# USB_Charger.net
KiCad netlist of a schematic drawn in EAGLE
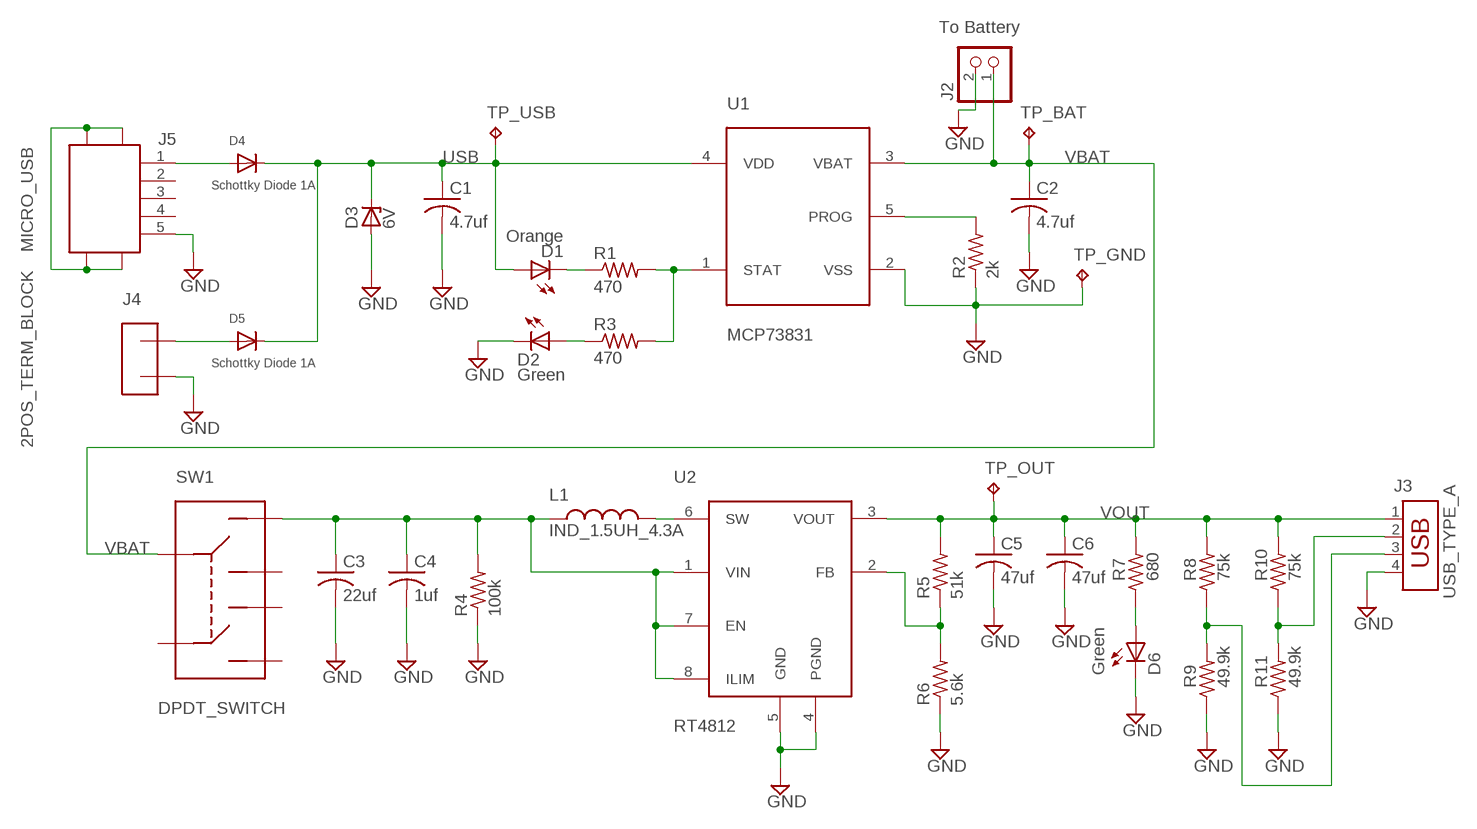
[diagram p0: schematic, sheet 1]

(export (version "E")
  (design (tool "Eeschema 10.0.6"))
  (components
    (comp (ref "C1")
      (value "4.7uf")
      (footprint "eagle-import:C0805")
      (libsource (lib "eagle-import") (part "C-USC0805"))
    )
    (comp (ref "C2")
      (value "4.7uf")
      (footprint "eagle-import:C0805")
      (libsource (lib "eagle-import") (part "C-USC0805"))
    )
    (comp (ref "C3")
      (value "22uf")
      (footprint "eagle-import:C0805")
      (libsource (lib "eagle-import") (part "C-USC0805"))
    )
    (comp (ref "C4")
      (value "1uf")
      (footprint "eagle-import:C0805")
      (libsource (lib "eagle-import") (part "C-USC0805"))
    )
    (comp (ref "C5")
      (value "47uf")
      (footprint "eagle-import:C1210")
      (libsource (lib "eagle-import") (part "C-USC1210"))
    )
    (comp (ref "C6")
      (value "47uf")
      (footprint "eagle-import:C1210")
      (libsource (lib "eagle-import") (part "C-USC1210"))
    )
    (comp (ref "D1")
      (value "Orange")
      (footprint "eagle-import:CHIP-LED0805")
      (libsource (lib "eagle-import") (part "LEDCHIP-LED0805"))
    )
    (comp (ref "D2")
      (value "Green")
      (footprint "eagle-import:CHIP-LED0805")
      (libsource (lib "eagle-import") (part "LEDCHIP-LED0805"))
    )
    (comp (ref "D3")
      (value "6V")
      (footprint "eagle-import:SMB")
      (libsource (lib "eagle-import") (part "ZENER-DIODESMB"))
    )
    (comp (ref "D4")
      (value "Schottky Diode 1A")
      (footprint "eagle-import:SMADIODE")
      (libsource (lib "eagle-import") (part "DIODESMA"))
    )
    (comp (ref "D5")
      (value "Schottky Diode 1A")
      (footprint "eagle-import:SMADIODE")
      (libsource (lib "eagle-import") (part "DIODESMA"))
    )
    (comp (ref "D6")
      (value "Green")
      (footprint "eagle-import:CHIP-LED0805")
      (libsource (lib "eagle-import") (part "LEDCHIP-LED0805"))
    )
    (comp (ref "J2")
      (value "To Battery")
      (footprint "eagle-import:JST-PH-2-THM-RA")
      (libsource (lib "eagle-import") (part "JST_2PIN-THM-RA"))
    )
    (comp (ref "J3")
      (value "USB_TYPE_A")
      (footprint "eagle-import:USB")
      (libsource (lib "eagle-import") (part "USB-787616"))
    )
    (comp (ref "J4")
      (value "2POS_TERM_BLOCK")
      (footprint "eagle-import:2POS_5.08MM")
      (libsource (lib "eagle-import") (part "2POS_TERM_BLOCK"))
    )
    (comp (ref "J5")
      (value "MICRO_USB")
      (footprint "eagle-import:MICRO_USB")
      (libsource (lib "eagle-import") (part "MICRO_USB"))
    )
    (comp (ref "L1")
      (value "IND_1.5UH_4.3A")
      (footprint "eagle-import:IND_SMD")
      (libsource (lib "eagle-import") (part "IND_1.5UH_4.3A"))
    )
    (comp (ref "R1")
      (value "470")
      (footprint "eagle-import:R0805")
      (libsource (lib "eagle-import") (part "R-US_R0805"))
    )
    (comp (ref "R2")
      (value "2k")
      (footprint "eagle-import:R0805")
      (libsource (lib "eagle-import") (part "R-US_R0805"))
    )
    (comp (ref "R3")
      (value "470")
      (footprint "eagle-import:R0805")
      (libsource (lib "eagle-import") (part "R-US_R0805"))
    )
    (comp (ref "R4")
      (value "100k")
      (footprint "eagle-import:R0805")
      (libsource (lib "eagle-import") (part "R-US_R0805"))
    )
    (comp (ref "R5")
      (value "51k")
      (footprint "eagle-import:R0805")
      (libsource (lib "eagle-import") (part "R-US_R0805"))
    )
    (comp (ref "R6")
      (value "5.6k")
      (footprint "eagle-import:R0805")
      (libsource (lib "eagle-import") (part "R-US_R0805"))
    )
    (comp (ref "R7")
      (value "680")
      (footprint "eagle-import:R0805")
      (libsource (lib "eagle-import") (part "R-US_R0805"))
    )
    (comp (ref "R8")
      (value "75k")
      (footprint "eagle-import:R0805")
      (libsource (lib "eagle-import") (part "R-US_R0805"))
    )
    (comp (ref "R9")
      (value "49.9k")
      (footprint "eagle-import:R0805")
      (libsource (lib "eagle-import") (part "R-US_R0805"))
    )
    (comp (ref "R10")
      (value "75k")
      (footprint "eagle-import:R0805")
      (libsource (lib "eagle-import") (part "R-US_R0805"))
    )
    (comp (ref "R11")
      (value "49.9k")
      (footprint "eagle-import:R0805")
      (libsource (lib "eagle-import") (part "R-US_R0805"))
    )
    (comp (ref "SW1")
      (value "DPDT_SWITCH")
      (footprint "eagle-import:GF-126-0159")
      (libsource (lib "eagle-import") (part "DPDT_SWITCH"))
    )
    (comp (ref "TP_BAT")
      (value "TPB1,27")
      (footprint "eagle-import:B1,27")
      (libsource (lib "eagle-import") (part "TPB1,27"))
    )
    (comp (ref "TP_GND")
      (value "TPB1,27")
      (footprint "eagle-import:B1,27")
      (libsource (lib "eagle-import") (part "TPB1,27"))
    )
    (comp (ref "TP_OUT")
      (value "TPB1,27")
      (footprint "eagle-import:B1,27")
      (libsource (lib "eagle-import") (part "TPB1,27"))
    )
    (comp (ref "TP_USB")
      (value "TPB1,27")
      (footprint "eagle-import:B1,27")
      (libsource (lib "eagle-import") (part "TPB1,27"))
    )
    (comp (ref "U1")
      (value "MCP73831")
      (footprint "eagle-import:SOT-23-5")
      (libsource (lib "eagle-import") (part "MCP73831"))
    )
    (comp (ref "U2")
      (value "RT4812")
      (footprint "eagle-import:TSOT-23-8")
      (libsource (lib "eagle-import") (part "RT4812"))
    )
  )
  (nets
    (net (code "1") (name "/USB") (class "Default")
      (node (ref "C1") (pin "1") (pinfunction "1_1") (pintype "passive"))
      (node (ref "D1") (pin "A") (pinfunction "A_A") (pintype "passive"))
      (node (ref "D3") (pin "C") (pinfunction "C_C") (pintype "passive"))
      (node (ref "D4") (pin "C") (pinfunction "C_C") (pintype "passive"))
      (node (ref "D5") (pin "C") (pinfunction "C_C") (pintype "passive"))
      (node (ref "TP_USB") (pin "TP") (pinfunction "TP_TP") (pintype "input"))
      (node (ref "U1") (pin "4") (pinfunction "VDD_4") (pintype "bidirectional"))
    )
    (net (code "2") (name "/VBAT") (class "Default")
      (node (ref "C2") (pin "1") (pinfunction "1_1") (pintype "passive"))
      (node (ref "J2") (pin "1") (pinfunction "2_1") (pintype "passive"))
      (node (ref "SW1") (pin "2") (pinfunction "2_2") (pintype "bidirectional"))
      (node (ref "TP_BAT") (pin "TP") (pinfunction "TP_TP") (pintype "input"))
      (node (ref "U1") (pin "3") (pinfunction "VBAT_3") (pintype "bidirectional"))
    )
    (net (code "3") (name "/VOUT") (class "Default")
      (node (ref "C5") (pin "1") (pinfunction "1_1") (pintype "passive"))
      (node (ref "C6") (pin "1") (pinfunction "1_1") (pintype "passive"))
      (node (ref "J3") (pin "1") (pinfunction "1_1") (pintype "passive"))
      (node (ref "R10") (pin "2") (pinfunction "2_2") (pintype "passive"))
      (node (ref "R5") (pin "2") (pinfunction "2_2") (pintype "passive"))
      (node (ref "R7") (pin "2") (pinfunction "2_2") (pintype "passive"))
      (node (ref "R8") (pin "2") (pinfunction "2_2") (pintype "passive"))
      (node (ref "TP_OUT") (pin "TP") (pinfunction "TP_TP") (pintype "input"))
      (node (ref "U2") (pin "3") (pinfunction "VOUT_3") (pintype "bidirectional"))
    )
    (net (code "4") (name "GND") (class "Default")
      (node (ref "C1") (pin "2") (pinfunction "2_2") (pintype "passive"))
      (node (ref "C2") (pin "2") (pinfunction "2_2") (pintype "passive"))
      (node (ref "C3") (pin "2") (pinfunction "2_2") (pintype "passive"))
      (node (ref "C4") (pin "2") (pinfunction "2_2") (pintype "passive"))
      (node (ref "C5") (pin "2") (pinfunction "2_2") (pintype "passive"))
      (node (ref "C6") (pin "2") (pinfunction "2_2") (pintype "passive"))
      (node (ref "D2") (pin "C") (pinfunction "C_C") (pintype "passive"))
      (node (ref "D3") (pin "A") (pinfunction "A_A") (pintype "passive"))
      (node (ref "D6") (pin "C") (pinfunction "C_C") (pintype "passive"))
      (node (ref "J2") (pin "2") (pinfunction "1_2") (pintype "passive"))
      (node (ref "J3") (pin "4") (pinfunction "4_4") (pintype "passive"))
      (node (ref "J4") (pin "2") (pinfunction "2_2") (pintype "bidirectional"))
      (node (ref "J5") (pin "5") (pinfunction "5_5") (pintype "bidirectional"))
      (node (ref "R11") (pin "1") (pinfunction "1_1") (pintype "passive"))
      (node (ref "R2") (pin "1") (pinfunction "1_1") (pintype "passive"))
      (node (ref "R4") (pin "1") (pinfunction "1_1") (pintype "passive"))
      (node (ref "R6") (pin "1") (pinfunction "1_1") (pintype "passive"))
      (node (ref "R9") (pin "1") (pinfunction "1_1") (pintype "passive"))
      (node (ref "TP_GND") (pin "TP") (pinfunction "TP_TP") (pintype "input"))
      (node (ref "U1") (pin "2") (pinfunction "VSS_2") (pintype "bidirectional"))
      (node (ref "U2") (pin "4") (pinfunction "PGND_4") (pintype "bidirectional"))
      (node (ref "U2") (pin "5") (pinfunction "GND_5") (pintype "bidirectional"))
    )
    (net (code "5") (name "Net-(D1-PadC)") (class "Default")
      (node (ref "D1") (pin "C") (pinfunction "C_C") (pintype "passive"))
      (node (ref "R1") (pin "1") (pinfunction "1_1") (pintype "passive"))
    )
    (net (code "6") (name "Net-(D2-PadA)") (class "Default")
      (node (ref "D2") (pin "A") (pinfunction "A_A") (pintype "passive"))
      (node (ref "R3") (pin "1") (pinfunction "1_1") (pintype "passive"))
    )
    (net (code "7") (name "Net-(D4-PadA)") (class "Default")
      (node (ref "D4") (pin "A") (pinfunction "A_A") (pintype "passive"))
      (node (ref "J5") (pin "1") (pinfunction "1_1") (pintype "bidirectional"))
    )
    (net (code "8") (name "Net-(D5-PadA)") (class "Default")
      (node (ref "D5") (pin "A") (pinfunction "A_A") (pintype "passive"))
      (node (ref "J4") (pin "1") (pinfunction "1_1") (pintype "bidirectional"))
    )
    (net (code "9") (name "Net-(D6-PadA)") (class "Default")
      (node (ref "D6") (pin "A") (pinfunction "A_A") (pintype "passive"))
      (node (ref "R7") (pin "1") (pinfunction "1_1") (pintype "passive"))
    )
    (net (code "10") (name "Net-(J3-Pad2)") (class "Default")
      (node (ref "J3") (pin "2") (pinfunction "2_2") (pintype "passive"))
      (node (ref "R10") (pin "1") (pinfunction "1_1") (pintype "passive"))
      (node (ref "R11") (pin "2") (pinfunction "2_2") (pintype "passive"))
    )
    (net (code "11") (name "Net-(J3-Pad3)") (class "Default")
      (node (ref "J3") (pin "3") (pinfunction "3_3") (pintype "passive"))
      (node (ref "R8") (pin "1") (pinfunction "1_1") (pintype "passive"))
      (node (ref "R9") (pin "2") (pinfunction "2_2") (pintype "passive"))
    )
    (net (code "12") (name "Net-(J5-PadSH1)") (class "Default")
      (node (ref "J5") (pin "SH1") (pinfunction "SH1_SH1") (pintype "bidirectional"))
      (node (ref "J5") (pin "SH2") (pinfunction "SH2_SH2") (pintype "bidirectional"))
      (node (ref "J5") (pin "SH3") (pinfunction "SH3_SH3") (pintype "bidirectional"))
      (node (ref "J5") (pin "SH4") (pinfunction "SH4_SH4") (pintype "bidirectional"))
    )
    (net (code "13") (name "Net-(U1-PROG)") (class "Default")
      (node (ref "R2") (pin "2") (pinfunction "2_2") (pintype "passive"))
      (node (ref "U1") (pin "5") (pinfunction "PROG_5") (pintype "bidirectional"))
    )
    (net (code "14") (name "Net-(U1-STAT)") (class "Default")
      (node (ref "R1") (pin "2") (pinfunction "2_2") (pintype "passive"))
      (node (ref "R3") (pin "2") (pinfunction "2_2") (pintype "passive"))
      (node (ref "U1") (pin "1") (pinfunction "STAT_1") (pintype "bidirectional"))
    )
    (net (code "15") (name "Net-(U2-EN)") (class "Default")
      (node (ref "C3") (pin "1") (pinfunction "1_1") (pintype "passive"))
      (node (ref "C4") (pin "1") (pinfunction "1_1") (pintype "passive"))
      (node (ref "L1") (pin "1") (pinfunction "1_1") (pintype "bidirectional"))
      (node (ref "R4") (pin "2") (pinfunction "2_2") (pintype "passive"))
      (node (ref "SW1") (pin "1") (pinfunction "1_1") (pintype "bidirectional"))
      (node (ref "U2") (pin "1") (pinfunction "VIN_1") (pintype "bidirectional"))
      (node (ref "U2") (pin "7") (pinfunction "EN_7") (pintype "bidirectional"))
      (node (ref "U2") (pin "8") (pinfunction "ILIM_8") (pintype "bidirectional"))
    )
    (net (code "16") (name "Net-(U2-FB)") (class "Default")
      (node (ref "R5") (pin "1") (pinfunction "1_1") (pintype "passive"))
      (node (ref "R6") (pin "2") (pinfunction "2_2") (pintype "passive"))
      (node (ref "U2") (pin "2") (pinfunction "FB_2") (pintype "bidirectional"))
    )
    (net (code "17") (name "Net-(U2-SW)") (class "Default")
      (node (ref "L1") (pin "2") (pinfunction "2_2") (pintype "bidirectional"))
      (node (ref "U2") (pin "6") (pinfunction "SW_6") (pintype "bidirectional"))
    )
    (net (code "18") (name "unconnected-(J5-Pad2)") (class "Default")
      (node (ref "J5") (pin "2") (pinfunction "2_2") (pintype "bidirectional"))
    )
    (net (code "19") (name "unconnected-(J5-Pad3)") (class "Default")
      (node (ref "J5") (pin "3") (pinfunction "3_3") (pintype "bidirectional"))
    )
    (net (code "20") (name "unconnected-(J5-Pad4)") (class "Default")
      (node (ref "J5") (pin "4") (pinfunction "4_4") (pintype "bidirectional"))
    )
    (net (code "21") (name "unconnected-(SW1-Pad3)") (class "Default")
      (node (ref "SW1") (pin "3") (pinfunction "3_3") (pintype "bidirectional"))
    )
    (net (code "22") (name "unconnected-(SW1-Pad4)") (class "Default")
      (node (ref "SW1") (pin "4") (pinfunction "4_4") (pintype "bidirectional"))
    )
    (net (code "23") (name "unconnected-(SW1-Pad5)") (class "Default")
      (node (ref "SW1") (pin "5") (pinfunction "5_5") (pintype "bidirectional"))
    )
    (net (code "24") (name "unconnected-(SW1-Pad6)") (class "Default")
      (node (ref "SW1") (pin "6") (pinfunction "6_6") (pintype "bidirectional"))
    )
  )
)
